# mughug.net
KiCad netlist of a schematic drawn in EAGLE
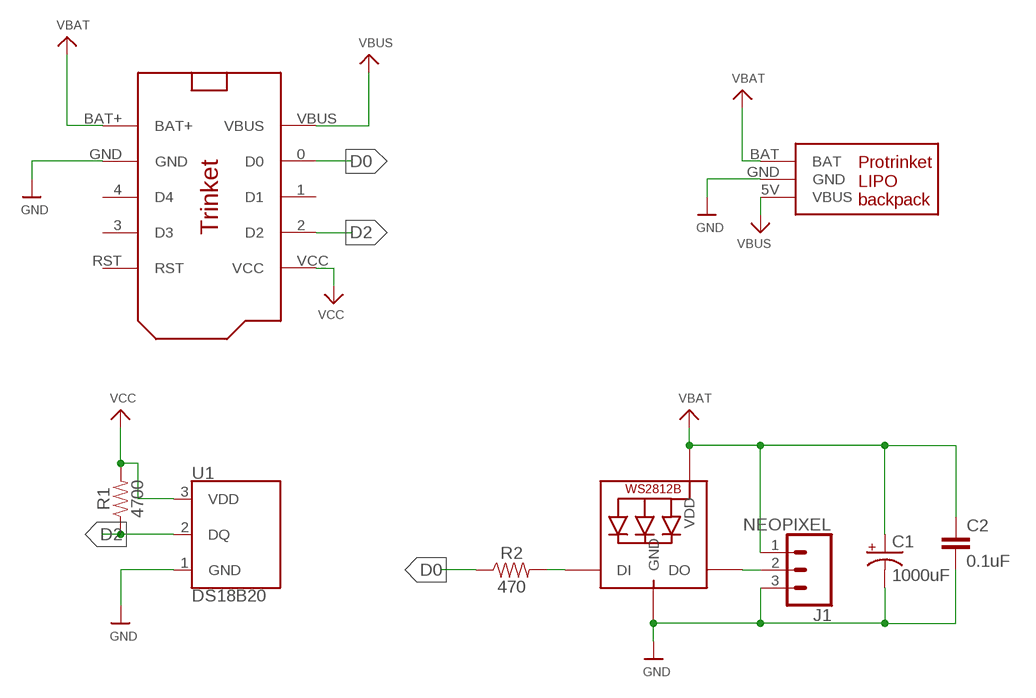
[diagram p0: schematic, sheet 1]

(export (version "E")
  (design (tool "Eeschema 10.0.6"))
  (components
    (comp (ref "C1")
      (value "1000uF")
      (footprint "eagle-import:150CLZ-0810")
      (libsource (lib "eagle-import") (part "CPOL-US150CLZ-0810"))
    )
    (comp (ref "C2")
      (value "0.1uF")
      (footprint "eagle-import:0603")
      (libsource (lib "eagle-import") (part "0.1UF-0603-25V-(+80/-20%)"))
    )
    (comp (ref "J1")
      (value "NEOPIXEL")
      (footprint "eagle-import:1X03")
      (libsource (lib "eagle-import") (part "CONN_03"))
    )
    (comp (ref "LED1")
      (value "WS2812B5050")
      (footprint "eagle-import:WS2812B")
      (libsource (lib "eagle-import") (part "WS2812B5050"))
    )
    (comp (ref "R1")
      (value "4700")
      (footprint "eagle-import:0603")
      (libsource (lib "eagle-import") (part "470OHM-0603-1/10W-1%"))
    )
    (comp (ref "R2")
      (value "470")
      (footprint "eagle-import:0603")
      (libsource (lib "eagle-import") (part "470OHM-0603-1/10W-1%"))
    )
    (comp (ref "U$1")
      (value "TRINKETNOHOLES")
      (footprint "eagle-import:TRINKET_NOHOLES")
      (libsource (lib "eagle-import") (part "TRINKETNOHOLES"))
    )
    (comp (ref "U$2")
      (value "PROTRINKETLIPO")
      (footprint "eagle-import:PROTRINKETLIPO_NOHOLE")
      (libsource (lib "eagle-import") (part "PROTRINKETLIPO"))
    )
    (comp (ref "U1")
      (value "DS18B20")
      (footprint "eagle-import:TO-92-AMMO")
      (libsource (lib "eagle-import") (part "DS18B20"))
    )
  )
  (nets
    (net (code "1") (name "D0") (class "Default")
      (node (ref "R2") (pin "1") (pinfunction "1_1") (pintype "passive"))
      (node (ref "U$1") (pin "0") (pinfunction "D0_0") (pintype "bidirectional"))
    )
    (net (code "2") (name "D2") (class "Default")
      (node (ref "R1") (pin "1") (pinfunction "1_1") (pintype "passive"))
      (node (ref "U$1") (pin "2") (pinfunction "D2_2") (pintype "bidirectional"))
      (node (ref "U1") (pin "2") (pinfunction "DQ_2") (pintype "bidirectional"))
    )
    (net (code "3") (name "GND") (class "Default")
      (node (ref "C1") (pin "-") (pinfunction "-_-") (pintype "passive"))
      (node (ref "C2") (pin "2") (pinfunction "2_2") (pintype "passive"))
      (node (ref "J1") (pin "3") (pinfunction "3_3") (pintype "passive"))
      (node (ref "LED1") (pin "3-GND") (pinfunction "GND_3-GND") (pintype "power_in"))
      (node (ref "U$1") (pin "GND") (pinfunction "GND_GND") (pintype "power_in"))
      (node (ref "U$2") (pin "GND") (pinfunction "GND_GND") (pintype "power_in"))
      (node (ref "U1") (pin "1") (pinfunction "GND_1") (pintype "power_in"))
    )
    (net (code "4") (name "Net-(LED1-DI)") (class "Default")
      (node (ref "LED1") (pin "4-DIN") (pinfunction "DI_4-DIN") (pintype "input"))
      (node (ref "R2") (pin "2") (pinfunction "2_2") (pintype "passive"))
    )
    (net (code "5") (name "Net-(LED1-DO)") (class "Default")
      (node (ref "J1") (pin "2") (pinfunction "2_2") (pintype "passive"))
      (node (ref "LED1") (pin "2-DOUT") (pinfunction "DO_2-DOUT") (pintype "output"))
    )
    (net (code "6") (name "VBAT") (class "Default")
      (node (ref "C1") (pin "+") (pinfunction "+_+") (pintype "passive"))
      (node (ref "C2") (pin "1") (pinfunction "1_1") (pintype "passive"))
      (node (ref "J1") (pin "1") (pinfunction "1_1") (pintype "passive"))
      (node (ref "LED1") (pin "1-VDD") (pinfunction "VDD_1-VDD") (pintype "power_in"))
      (node (ref "U$1") (pin "BAT+") (pinfunction "BAT+_BAT+") (pintype "power_in"))
      (node (ref "U$2") (pin "BAT") (pinfunction "BAT_BAT") (pintype "power_in"))
    )
    (net (code "7") (name "VBUS") (class "Default")
      (node (ref "U$1") (pin "VBUS") (pinfunction "VBUS_VBUS") (pintype "power_in"))
      (node (ref "U$2") (pin "5V") (pinfunction "VBUS_5V") (pintype "power_in"))
    )
    (net (code "8") (name "VCC") (class "Default")
      (node (ref "R1") (pin "2") (pinfunction "2_2") (pintype "passive"))
      (node (ref "U$1") (pin "VCC") (pinfunction "VCC_VCC") (pintype "power_in"))
      (node (ref "U1") (pin "3") (pinfunction "VDD_3") (pintype "power_in"))
    )
    (net (code "9") (name "unconnected-(U$1-D1-Pad1)") (class "Default")
      (node (ref "U$1") (pin "1") (pinfunction "D1_1") (pintype "bidirectional"))
    )
    (net (code "10") (name "unconnected-(U$1-D3-Pad3)") (class "Default")
      (node (ref "U$1") (pin "3") (pinfunction "D3_3") (pintype "bidirectional"))
    )
    (net (code "11") (name "unconnected-(U$1-D4-Pad4)") (class "Default")
      (node (ref "U$1") (pin "4") (pinfunction "D4_4") (pintype "bidirectional"))
    )
    (net (code "12") (name "unconnected-(U$1-PadRST)") (class "Default")
      (node (ref "U$1") (pin "RST") (pinfunction "RST_RST") (pintype "passive"))
    )
  )
)
